# CON_MC_XMC_J13_64PIN.net
KiCad netlist of a schematic drawn in Altium Designer
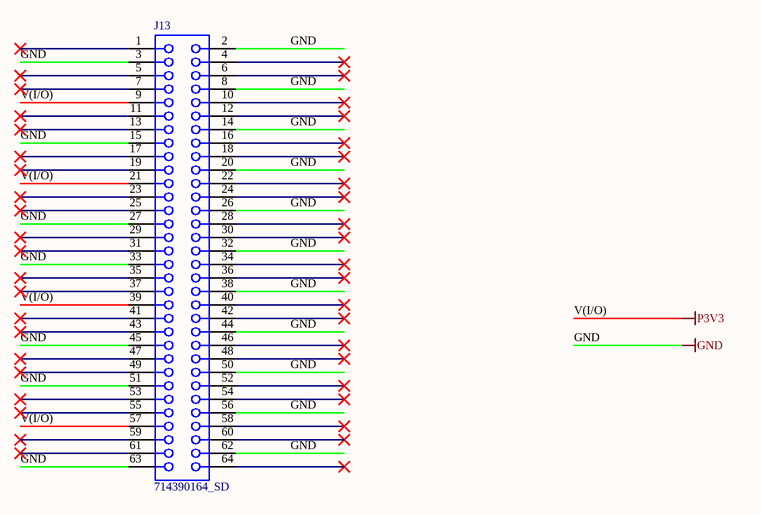
[diagram p0: CON_MC_XMC_J13_64PIN.SchDoc]

(export (version "E")
  (design (tool "Eeschema 10.0.6"))
  (components
    (comp (ref "J13")
      (value "714390164_SD")
      (footprint "BTB1-2V64F")
      (description "Board-to-Board Connector, Vertical, 2-Row, Pitch 1mm, 64-Position, Female")
      (fields (field (name "PUBLISHER") "Altium"))
      (libsource (lib "Altium Shanghai") (part "CMP-0001-00081-1"))
    )
  )
  (nets
    (net (code "1") (name "GND") (class "Default")
      (node (ref "J13") (pin "14") (pinfunction "14_14") (pintype "passive"))
      (node (ref "J13") (pin "15") (pinfunction "15_15") (pintype "passive"))
      (node (ref "J13") (pin "2") (pinfunction "2_2") (pintype "passive"))
      (node (ref "J13") (pin "20") (pinfunction "20_20") (pintype "passive"))
      (node (ref "J13") (pin "26") (pinfunction "26_26") (pintype "passive"))
      (node (ref "J13") (pin "27") (pinfunction "27_27") (pintype "passive"))
      (node (ref "J13") (pin "3") (pinfunction "3_3") (pintype "passive"))
      (node (ref "J13") (pin "32") (pinfunction "32_32") (pintype "passive"))
      (node (ref "J13") (pin "33") (pinfunction "33_33") (pintype "passive"))
      (node (ref "J13") (pin "38") (pinfunction "38_38") (pintype "passive"))
      (node (ref "J13") (pin "44") (pinfunction "44_44") (pintype "passive"))
      (node (ref "J13") (pin "45") (pinfunction "45_45") (pintype "passive"))
      (node (ref "J13") (pin "50") (pinfunction "50_50") (pintype "passive"))
      (node (ref "J13") (pin "51") (pinfunction "51_51") (pintype "passive"))
      (node (ref "J13") (pin "56") (pinfunction "56_56") (pintype "passive"))
      (node (ref "J13") (pin "62") (pinfunction "62_62") (pintype "passive"))
      (node (ref "J13") (pin "63") (pinfunction "63_63") (pintype "passive"))
      (node (ref "J13") (pin "8") (pinfunction "8_8") (pintype "passive"))
    )
    (net (code "2") (name "P3V3") (class "Default")
      (node (ref "J13") (pin "21") (pinfunction "21_21") (pintype "passive"))
      (node (ref "J13") (pin "39") (pinfunction "39_39") (pintype "passive"))
      (node (ref "J13") (pin "57") (pinfunction "57_57") (pintype "passive"))
      (node (ref "J13") (pin "9") (pinfunction "9_9") (pintype "passive"))
    )
    (net (code "3") (name "unconnected-(J13-Pad1)") (class "Default")
      (node (ref "J13") (pin "1") (pinfunction "1_1") (pintype "passive+no_connect"))
    )
    (net (code "4") (name "unconnected-(J13-Pad4)") (class "Default")
      (node (ref "J13") (pin "4") (pinfunction "4_4") (pintype "passive+no_connect"))
    )
    (net (code "5") (name "unconnected-(J13-Pad5)") (class "Default")
      (node (ref "J13") (pin "5") (pinfunction "5_5") (pintype "passive+no_connect"))
    )
    (net (code "6") (name "unconnected-(J13-Pad6)") (class "Default")
      (node (ref "J13") (pin "6") (pinfunction "6_6") (pintype "passive+no_connect"))
    )
    (net (code "7") (name "unconnected-(J13-Pad7)") (class "Default")
      (node (ref "J13") (pin "7") (pinfunction "7_7") (pintype "passive+no_connect"))
    )
    (net (code "8") (name "unconnected-(J13-Pad10)") (class "Default")
      (node (ref "J13") (pin "10") (pinfunction "10_10") (pintype "passive+no_connect"))
    )
    (net (code "9") (name "unconnected-(J13-Pad11)") (class "Default")
      (node (ref "J13") (pin "11") (pinfunction "11_11") (pintype "passive+no_connect"))
    )
    (net (code "10") (name "unconnected-(J13-Pad12)") (class "Default")
      (node (ref "J13") (pin "12") (pinfunction "12_12") (pintype "passive+no_connect"))
    )
    (net (code "11") (name "unconnected-(J13-Pad13)") (class "Default")
      (node (ref "J13") (pin "13") (pinfunction "13_13") (pintype "passive+no_connect"))
    )
    (net (code "12") (name "unconnected-(J13-Pad16)") (class "Default")
      (node (ref "J13") (pin "16") (pinfunction "16_16") (pintype "passive+no_connect"))
    )
    (net (code "13") (name "unconnected-(J13-Pad17)") (class "Default")
      (node (ref "J13") (pin "17") (pinfunction "17_17") (pintype "passive+no_connect"))
    )
    (net (code "14") (name "unconnected-(J13-Pad18)") (class "Default")
      (node (ref "J13") (pin "18") (pinfunction "18_18") (pintype "passive+no_connect"))
    )
    (net (code "15") (name "unconnected-(J13-Pad19)") (class "Default")
      (node (ref "J13") (pin "19") (pinfunction "19_19") (pintype "passive+no_connect"))
    )
    (net (code "16") (name "unconnected-(J13-Pad22)") (class "Default")
      (node (ref "J13") (pin "22") (pinfunction "22_22") (pintype "passive+no_connect"))
    )
    (net (code "17") (name "unconnected-(J13-Pad23)") (class "Default")
      (node (ref "J13") (pin "23") (pinfunction "23_23") (pintype "passive+no_connect"))
    )
    (net (code "18") (name "unconnected-(J13-Pad24)") (class "Default")
      (node (ref "J13") (pin "24") (pinfunction "24_24") (pintype "passive+no_connect"))
    )
    (net (code "19") (name "unconnected-(J13-Pad25)") (class "Default")
      (node (ref "J13") (pin "25") (pinfunction "25_25") (pintype "passive+no_connect"))
    )
    (net (code "20") (name "unconnected-(J13-Pad28)") (class "Default")
      (node (ref "J13") (pin "28") (pinfunction "28_28") (pintype "passive+no_connect"))
    )
    (net (code "21") (name "unconnected-(J13-Pad29)") (class "Default")
      (node (ref "J13") (pin "29") (pinfunction "29_29") (pintype "passive+no_connect"))
    )
    (net (code "22") (name "unconnected-(J13-Pad30)") (class "Default")
      (node (ref "J13") (pin "30") (pinfunction "30_30") (pintype "passive+no_connect"))
    )
    (net (code "23") (name "unconnected-(J13-Pad31)") (class "Default")
      (node (ref "J13") (pin "31") (pinfunction "31_31") (pintype "passive+no_connect"))
    )
    (net (code "24") (name "unconnected-(J13-Pad34)") (class "Default")
      (node (ref "J13") (pin "34") (pinfunction "34_34") (pintype "passive+no_connect"))
    )
    (net (code "25") (name "unconnected-(J13-Pad35)") (class "Default")
      (node (ref "J13") (pin "35") (pinfunction "35_35") (pintype "passive+no_connect"))
    )
    (net (code "26") (name "unconnected-(J13-Pad36)") (class "Default")
      (node (ref "J13") (pin "36") (pinfunction "36_36") (pintype "passive+no_connect"))
    )
    (net (code "27") (name "unconnected-(J13-Pad37)") (class "Default")
      (node (ref "J13") (pin "37") (pinfunction "37_37") (pintype "passive+no_connect"))
    )
    (net (code "28") (name "unconnected-(J13-Pad40)") (class "Default")
      (node (ref "J13") (pin "40") (pinfunction "40_40") (pintype "passive+no_connect"))
    )
    (net (code "29") (name "unconnected-(J13-Pad41)") (class "Default")
      (node (ref "J13") (pin "41") (pinfunction "41_41") (pintype "passive+no_connect"))
    )
    (net (code "30") (name "unconnected-(J13-Pad42)") (class "Default")
      (node (ref "J13") (pin "42") (pinfunction "42_42") (pintype "passive+no_connect"))
    )
    (net (code "31") (name "unconnected-(J13-Pad43)") (class "Default")
      (node (ref "J13") (pin "43") (pinfunction "43_43") (pintype "passive+no_connect"))
    )
    (net (code "32") (name "unconnected-(J13-Pad46)") (class "Default")
      (node (ref "J13") (pin "46") (pinfunction "46_46") (pintype "passive+no_connect"))
    )
    (net (code "33") (name "unconnected-(J13-Pad47)") (class "Default")
      (node (ref "J13") (pin "47") (pinfunction "47_47") (pintype "passive+no_connect"))
    )
    (net (code "34") (name "unconnected-(J13-Pad48)") (class "Default")
      (node (ref "J13") (pin "48") (pinfunction "48_48") (pintype "passive+no_connect"))
    )
    (net (code "35") (name "unconnected-(J13-Pad49)") (class "Default")
      (node (ref "J13") (pin "49") (pinfunction "49_49") (pintype "passive+no_connect"))
    )
    (net (code "36") (name "unconnected-(J13-Pad52)") (class "Default")
      (node (ref "J13") (pin "52") (pinfunction "52_52") (pintype "passive+no_connect"))
    )
    (net (code "37") (name "unconnected-(J13-Pad53)") (class "Default")
      (node (ref "J13") (pin "53") (pinfunction "53_53") (pintype "passive+no_connect"))
    )
    (net (code "38") (name "unconnected-(J13-Pad54)") (class "Default")
      (node (ref "J13") (pin "54") (pinfunction "54_54") (pintype "passive+no_connect"))
    )
    (net (code "39") (name "unconnected-(J13-Pad55)") (class "Default")
      (node (ref "J13") (pin "55") (pinfunction "55_55") (pintype "passive+no_connect"))
    )
    (net (code "40") (name "unconnected-(J13-Pad58)") (class "Default")
      (node (ref "J13") (pin "58") (pinfunction "58_58") (pintype "passive+no_connect"))
    )
    (net (code "41") (name "unconnected-(J13-Pad59)") (class "Default")
      (node (ref "J13") (pin "59") (pinfunction "59_59") (pintype "passive+no_connect"))
    )
    (net (code "42") (name "unconnected-(J13-Pad60)") (class "Default")
      (node (ref "J13") (pin "60") (pinfunction "60_60") (pintype "passive+no_connect"))
    )
    (net (code "43") (name "unconnected-(J13-Pad61)") (class "Default")
      (node (ref "J13") (pin "61") (pinfunction "61_61") (pintype "passive+no_connect"))
    )
    (net (code "44") (name "unconnected-(J13-Pad64)") (class "Default")
      (node (ref "J13") (pin "64") (pinfunction "64_64") (pintype "passive+no_connect"))
    )
  )
)
